# FET_bord.net
KiCad netlist of a schematic drawn in EAGLE
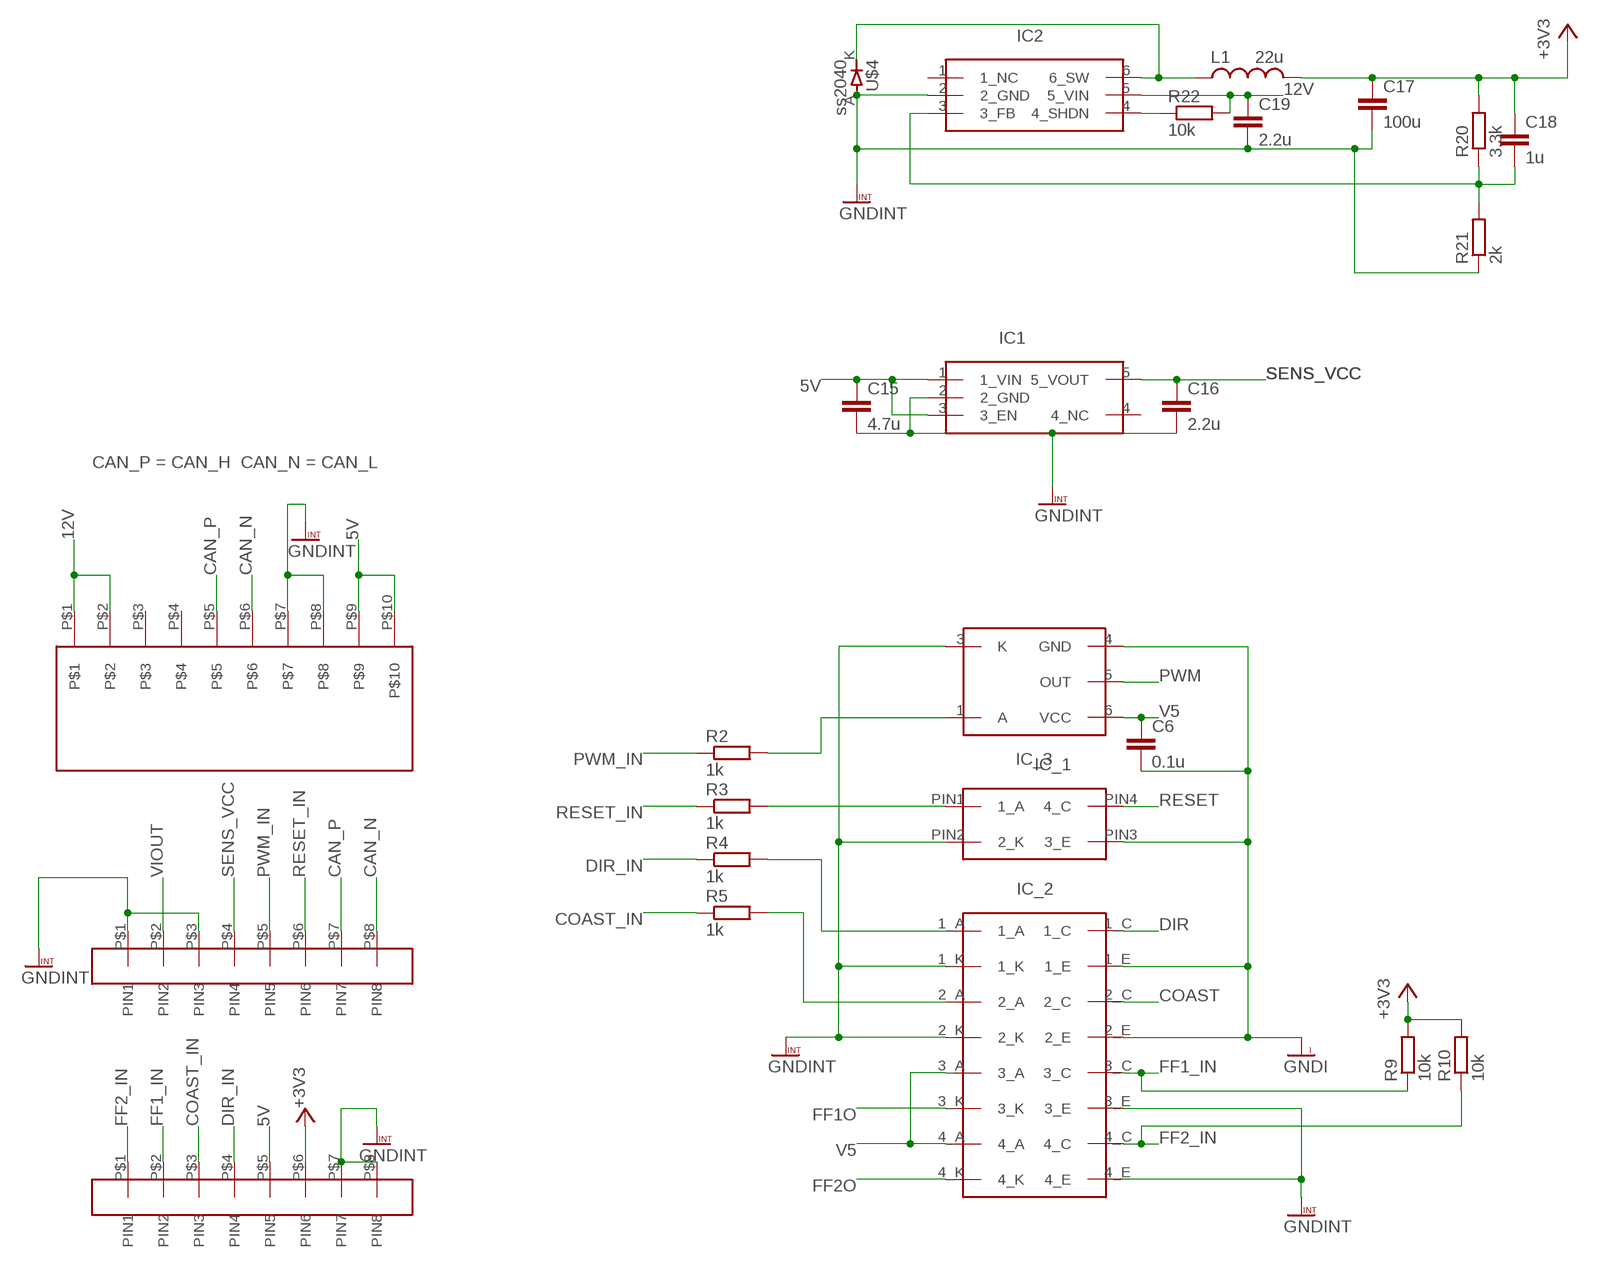
[diagram p0: schematic, sheet 1, part 1 of 2]
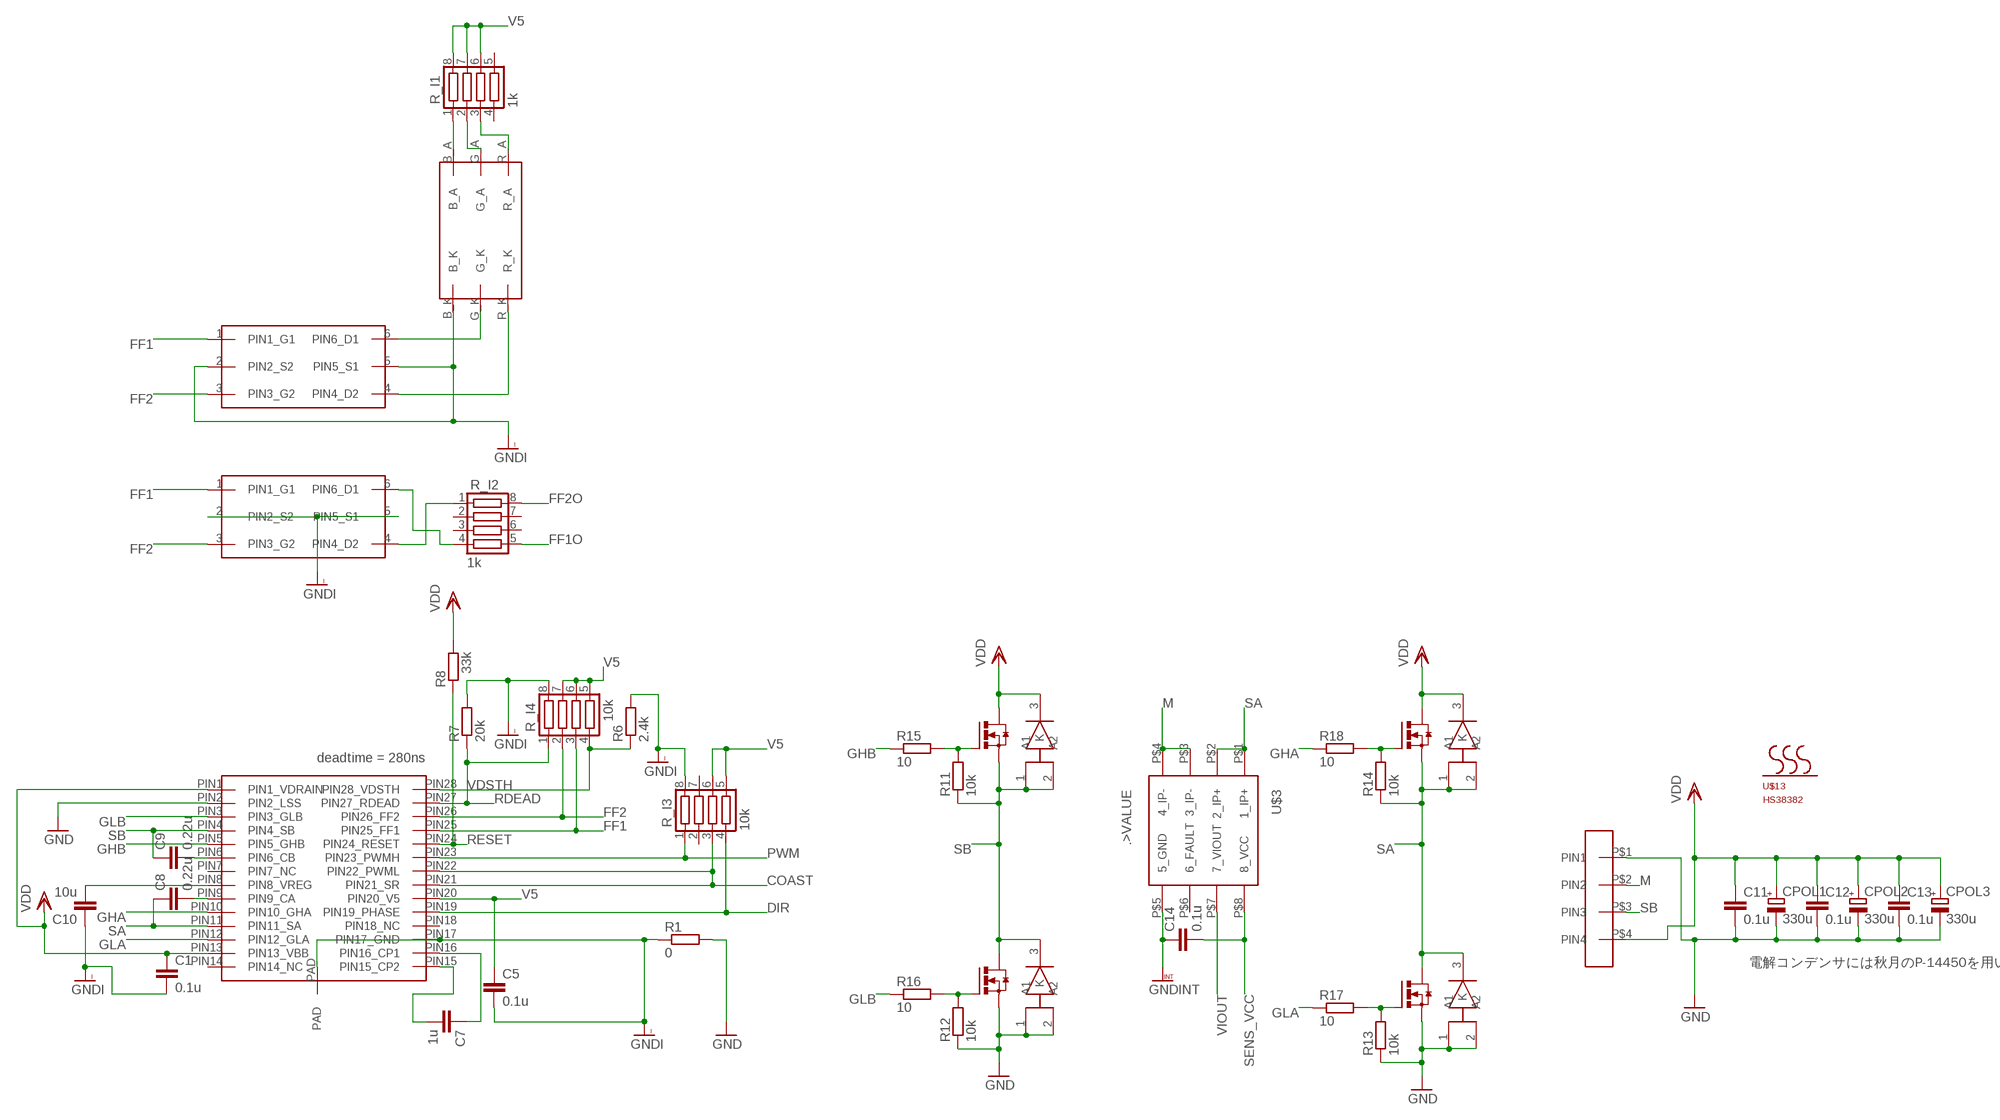
[diagram p1: schematic, sheet 1, part 2 of 2]

(export (version "E")
  (design (tool "Eeschema 10.0.6"))
  (components
    (comp (ref "C1")
      (value "0.1u")
      (footprint "eagle-import:C1608")
      (libsource (lib "eagle-import") (part "C-EUC1608"))
    )
    (comp (ref "C5")
      (value "0.1u")
      (footprint "eagle-import:C1608")
      (libsource (lib "eagle-import") (part "C-EUC1608"))
    )
    (comp (ref "C6")
      (value "0.1u")
      (footprint "eagle-import:C1608")
      (libsource (lib "eagle-import") (part "C-EUC1608"))
    )
    (comp (ref "C7")
      (value "1u")
      (footprint "eagle-import:C1608")
      (libsource (lib "eagle-import") (part "C-EUC1608"))
    )
    (comp (ref "C8")
      (value "0.22u")
      (footprint "eagle-import:C1608")
      (libsource (lib "eagle-import") (part "C-EUC1608"))
    )
    (comp (ref "C9")
      (value "0.22u")
      (footprint "eagle-import:C1608")
      (libsource (lib "eagle-import") (part "C-EUC1608"))
    )
    (comp (ref "C10")
      (value "10u")
      (footprint "eagle-import:C1608")
      (libsource (lib "eagle-import") (part "C-EUC1608"))
    )
    (comp (ref "C11")
      (value "0.1u")
      (footprint "eagle-import:C1608")
      (libsource (lib "eagle-import") (part "C-EUC1608"))
    )
    (comp (ref "C12")
      (value "0.1u")
      (footprint "eagle-import:C1608")
      (libsource (lib "eagle-import") (part "C-EUC1608"))
    )
    (comp (ref "C13")
      (value "0.1u")
      (footprint "eagle-import:C1608")
      (libsource (lib "eagle-import") (part "C-EUC1608"))
    )
    (comp (ref "C14")
      (value "0.1u")
      (footprint "eagle-import:C1608")
      (libsource (lib "eagle-import") (part "C-EUC1608"))
    )
    (comp (ref "C15")
      (value "4.7u")
      (footprint "eagle-import:C1608")
      (libsource (lib "eagle-import") (part "C-EUC1608"))
    )
    (comp (ref "C16")
      (value "2.2u")
      (footprint "eagle-import:C1608")
      (libsource (lib "eagle-import") (part "C-EUC1608"))
    )
    (comp (ref "C17")
      (value "100u")
      (footprint "eagle-import:C3216")
      (libsource (lib "eagle-import") (part "C-EUC3216"))
    )
    (comp (ref "C18")
      (value "1u")
      (footprint "eagle-import:C1608")
      (libsource (lib "eagle-import") (part "C-EUC1608"))
    )
    (comp (ref "C19")
      (value "2.2u")
      (footprint "eagle-import:C1608")
      (libsource (lib "eagle-import") (part "C-EUC1608"))
    )
    (comp (ref "CON1")
      (value "JQ_P8P")
      (footprint "eagle-import:JQ_P8P")
      (libsource (lib "eagle-import") (part "JQ_P8P"))
    )
    (comp (ref "CON2")
      (value "JQ_P8P")
      (footprint "eagle-import:JQ_P8P")
      (libsource (lib "eagle-import") (part "JQ_P8P"))
    )
    (comp (ref "CPOL1")
      (value "330u")
      (footprint "eagle-import:1014CAPA")
      (libsource (lib "eagle-import") (part "C_DEKAI"))
    )
    (comp (ref "CPOL2")
      (value "330u")
      (footprint "eagle-import:1014CAPA")
      (libsource (lib "eagle-import") (part "C_DEKAI"))
    )
    (comp (ref "CPOL3")
      (value "330u")
      (footprint "eagle-import:1014CAPA")
      (libsource (lib "eagle-import") (part "C_DEKAI"))
    )
    (comp (ref "IC1")
      (value "ADP151AUJZ")
      (footprint "eagle-import:SOT23-5")
      (libsource (lib "eagle-import") (part "ADP151AUJZ"))
    )
    (comp (ref "IC2")
      (value "NJW1616T")
      (footprint "eagle-import:SOT23-6")
      (libsource (lib "eagle-import") (part "NJW1616T"))
    )
    (comp (ref "IC_1")
      (value "TLP291")
      (footprint "eagle-import:TLP291")
      (libsource (lib "eagle-import") (part "TLP291"))
    )
    (comp (ref "IC_2")
      (value "TLP290-4")
      (footprint "eagle-import:TLP290")
      (libsource (lib "eagle-import") (part "TLP290-4"))
    )
    (comp (ref "IC_3")
      (value "TLP152")
      (footprint "eagle-import:SO6-5")
      (libsource (lib "eagle-import") (part "TLP152"))
    )
    (comp (ref "L1")
      (value "22u")
      (footprint "eagle-import:SMD_INDUCTOR")
      (libsource (lib "eagle-import") (part "L_SMD_INDUCTOR"))
    )
    (comp (ref "R1")
      (value "0")
      (footprint "eagle-import:1608")
      (libsource (lib "eagle-import") (part "R_REG"))
    )
    (comp (ref "R2")
      (value "1k")
      (footprint "eagle-import:1608")
      (libsource (lib "eagle-import") (part "R_REG"))
    )
    (comp (ref "R3")
      (value "1k")
      (footprint "eagle-import:1608")
      (libsource (lib "eagle-import") (part "R_REG"))
    )
    (comp (ref "R4")
      (value "1k")
      (footprint "eagle-import:1608")
      (libsource (lib "eagle-import") (part "R_REG"))
    )
    (comp (ref "R5")
      (value "1k")
      (footprint "eagle-import:1608")
      (libsource (lib "eagle-import") (part "R_REG"))
    )
    (comp (ref "R6")
      (value "2.4k")
      (footprint "eagle-import:1608")
      (libsource (lib "eagle-import") (part "R_REG"))
    )
    (comp (ref "R7")
      (value "20k")
      (footprint "eagle-import:1608")
      (libsource (lib "eagle-import") (part "R_REG"))
    )
    (comp (ref "R8")
      (value "33k")
      (footprint "eagle-import:1608")
      (libsource (lib "eagle-import") (part "R_REG"))
    )
    (comp (ref "R9")
      (value "10k")
      (footprint "eagle-import:1608")
      (libsource (lib "eagle-import") (part "R_REG"))
    )
    (comp (ref "R10")
      (value "10k")
      (footprint "eagle-import:1608")
      (libsource (lib "eagle-import") (part "R_REG"))
    )
    (comp (ref "R11")
      (value "10k")
      (footprint "eagle-import:1608")
      (libsource (lib "eagle-import") (part "R_REG"))
    )
    (comp (ref "R12")
      (value "10k")
      (footprint "eagle-import:1608")
      (libsource (lib "eagle-import") (part "R_REG"))
    )
    (comp (ref "R13")
      (value "10k")
      (footprint "eagle-import:1608")
      (libsource (lib "eagle-import") (part "R_REG"))
    )
    (comp (ref "R14")
      (value "10k")
      (footprint "eagle-import:1608")
      (libsource (lib "eagle-import") (part "R_REG"))
    )
    (comp (ref "R15")
      (value "10")
      (footprint "eagle-import:1608")
      (libsource (lib "eagle-import") (part "R_REG"))
    )
    (comp (ref "R16")
      (value "10")
      (footprint "eagle-import:1608")
      (libsource (lib "eagle-import") (part "R_REG"))
    )
    (comp (ref "R17")
      (value "10")
      (footprint "eagle-import:1608")
      (libsource (lib "eagle-import") (part "R_REG"))
    )
    (comp (ref "R18")
      (value "10")
      (footprint "eagle-import:1608")
      (libsource (lib "eagle-import") (part "R_REG"))
    )
    (comp (ref "R20")
      (value "3.3k")
      (footprint "eagle-import:1608")
      (libsource (lib "eagle-import") (part "R_REG"))
    )
    (comp (ref "R21")
      (value "2k")
      (footprint "eagle-import:1608")
      (libsource (lib "eagle-import") (part "R_REG"))
    )
    (comp (ref "R22")
      (value "10k")
      (footprint "eagle-import:1608")
      (libsource (lib "eagle-import") (part "R_REG"))
    )
    (comp (ref "R_I1")
      (value "1k")
      (footprint "eagle-import:0603X4RESISTOR")
      (libsource (lib "eagle-import") (part "R_SHUGOU"))
    )
    (comp (ref "R_I2")
      (value "1k")
      (footprint "eagle-import:0603X4RESISTOR")
      (libsource (lib "eagle-import") (part "R_SHUGOU"))
    )
    (comp (ref "R_I3")
      (value "10k")
      (footprint "eagle-import:1005X4RESISTOR")
      (libsource (lib "eagle-import") (part "R_SHUGOU2"))
    )
    (comp (ref "R_I4")
      (value "10k")
      (footprint "eagle-import:1005X4RESISTOR")
      (libsource (lib "eagle-import") (part "R_SHUGOU2"))
    )
    (comp (ref "TR1")
      (value "SKI03021")
      (footprint "eagle-import:D2PACK")
      (libsource (lib "eagle-import") (part "SKI03021"))
    )
    (comp (ref "TR2")
      (value "SKI03021")
      (footprint "eagle-import:D2PACK")
      (libsource (lib "eagle-import") (part "SKI03021"))
    )
    (comp (ref "TR3")
      (value "SKI03021")
      (footprint "eagle-import:D2PACK")
      (libsource (lib "eagle-import") (part "SKI03021"))
    )
    (comp (ref "TR4")
      (value "SKI03021")
      (footprint "eagle-import:D2PACK")
      (libsource (lib "eagle-import") (part "SKI03021"))
    )
    (comp (ref "U$1")
      (value "VL_4P")
      (footprint "eagle-import:VL_4P")
      (libsource (lib "eagle-import") (part "VL_4P"))
    )
    (comp (ref "U$2")
      (value "A3921")
      (footprint "eagle-import:TSSOP_28P_ALLEGRO")
      (libsource (lib "eagle-import") (part "A3921"))
    )
    (comp (ref "U$3")
      (value "ACS711")
      (footprint "eagle-import:SOIC8")
      (libsource (lib "eagle-import") (part "ACS711"))
    )
    (comp (ref "U$4")
      (value "ss2040")
      (footprint "eagle-import:SOD_123")
      (libsource (lib "eagle-import") (part "SMD_DAIOD"))
    )
    (comp (ref "U$5")
      (value "FDC6305")
      (footprint "eagle-import:SSOT6")
      (libsource (lib "eagle-import") (part "FDC6305"))
    )
    (comp (ref "U$6")
      (value "RGB_LED")
      (footprint "eagle-import:RGB_LED")
      (libsource (lib "eagle-import") (part "RGB_LED"))
    )
    (comp (ref "U$7")
      (value "FDC6305")
      (footprint "eagle-import:SSOT6")
      (libsource (lib "eagle-import") (part "FDC6305"))
    )
    (comp (ref "U$8")
      (value "BOX10PBOX10P-L")
      (footprint "eagle-import:BOX10P-L")
      (libsource (lib "eagle-import") (part "BOX10PBOX10P-L"))
    )
    (comp (ref "U$9")
      (value "SBR15U30SP5")
      (footprint "eagle-import:POWERDI_5")
      (libsource (lib "eagle-import") (part "SBR15U30SP5"))
    )
    (comp (ref "U$10")
      (value "SBR15U30SP5")
      (footprint "eagle-import:POWERDI_5")
      (libsource (lib "eagle-import") (part "SBR15U30SP5"))
    )
    (comp (ref "U$11")
      (value "SBR15U30SP5")
      (footprint "eagle-import:POWERDI_5")
      (libsource (lib "eagle-import") (part "SBR15U30SP5"))
    )
    (comp (ref "U$12")
      (value "SBR15U30SP5")
      (footprint "eagle-import:POWERDI_5")
      (libsource (lib "eagle-import") (part "SBR15U30SP5"))
    )
    (comp (ref "U$13")
      (value "HS38382")
      (footprint "eagle-import:38X38SQ")
      (libsource (lib "eagle-import") (part "HS38382"))
    )
  )
  (nets
    (net (code "1") (name "+3V3") (class "Default")
      (node (ref "C17") (pin "1") (pinfunction "1_1") (pintype "passive"))
      (node (ref "C18") (pin "1") (pinfunction "1_1") (pintype "passive"))
      (node (ref "CON1") (pin "P$6") (pinfunction "PIN6_P$6") (pintype "bidirectional"))
      (node (ref "L1") (pin "P$2") (pinfunction "2_P$2") (pintype "passive"))
      (node (ref "R10") (pin "2") (pinfunction "2_2") (pintype "passive"))
      (node (ref "R20") (pin "2") (pinfunction "2_2") (pintype "passive"))
      (node (ref "R9") (pin "2") (pinfunction "2_2") (pintype "passive"))
    )
    (net (code "2") (name "/5V") (class "Default")
      (node (ref "C15") (pin "1") (pinfunction "1_1") (pintype "passive"))
      (node (ref "CON1") (pin "P$5") (pinfunction "PIN5_P$5") (pintype "bidirectional"))
      (node (ref "IC1") (pin "1") (pinfunction "1_VIN_1") (pintype "bidirectional"))
      (node (ref "IC1") (pin "3") (pinfunction "3_EN_3") (pintype "bidirectional"))
      (node (ref "U$8") (pin "P$10") (pinfunction "P$10_P$10") (pintype "bidirectional"))
      (node (ref "U$8") (pin "P$9") (pinfunction "P$9_P$9") (pintype "bidirectional"))
    )
    (net (code "3") (name "/12V") (class "Default")
      (node (ref "C19") (pin "1") (pinfunction "1_1") (pintype "passive"))
      (node (ref "IC2") (pin "5") (pinfunction "5_VIN_5") (pintype "bidirectional"))
      (node (ref "R22") (pin "2") (pinfunction "2_2") (pintype "passive"))
      (node (ref "U$8") (pin "P$1") (pinfunction "P$1_P$1") (pintype "bidirectional"))
      (node (ref "U$8") (pin "P$2") (pinfunction "P$2_P$2") (pintype "bidirectional"))
    )
    (net (code "4") (name "/CAN_N") (class "Default")
      (node (ref "CON2") (pin "P$8") (pinfunction "PIN8_P$8") (pintype "bidirectional"))
      (node (ref "U$8") (pin "P$6") (pinfunction "P$6_P$6") (pintype "bidirectional"))
    )
    (net (code "5") (name "/CAN_P") (class "Default")
      (node (ref "CON2") (pin "P$7") (pinfunction "PIN7_P$7") (pintype "bidirectional"))
      (node (ref "U$8") (pin "P$5") (pinfunction "P$5_P$5") (pintype "bidirectional"))
    )
    (net (code "6") (name "/COAST") (class "Default")
      (node (ref "IC_2") (pin "2_C") (pinfunction "2_C_2_C") (pintype "bidirectional"))
      (node (ref "R_I3") (pin "3") (pinfunction "3_3") (pintype "passive"))
      (node (ref "U$2") (pin "PIN21") (pinfunction "PIN21_SR_PIN21") (pintype "bidirectional"))
      (node (ref "U$2") (pin "PIN22") (pinfunction "PIN22_PWML_PIN22") (pintype "bidirectional"))
    )
    (net (code "7") (name "/COAST_IN") (class "Default")
      (node (ref "CON1") (pin "P$3") (pinfunction "PIN3_P$3") (pintype "bidirectional"))
      (node (ref "R5") (pin "1") (pinfunction "1_1") (pintype "passive"))
    )
    (net (code "8") (name "/DIR") (class "Default")
      (node (ref "IC_2") (pin "1_C") (pinfunction "1_C_1_C") (pintype "bidirectional"))
      (node (ref "R_I3") (pin "4") (pinfunction "4_4") (pintype "passive"))
      (node (ref "U$2") (pin "PIN19") (pinfunction "PIN19_PHASE_PIN19") (pintype "bidirectional"))
    )
    (net (code "9") (name "/DIR_IN") (class "Default")
      (node (ref "CON1") (pin "P$4") (pinfunction "PIN4_P$4") (pintype "bidirectional"))
      (node (ref "R4") (pin "1") (pinfunction "1_1") (pintype "passive"))
    )
    (net (code "10") (name "/FF1") (class "Default")
      (node (ref "R_I4") (pin "3") (pinfunction "3_3") (pintype "passive"))
      (node (ref "U$2") (pin "PIN25") (pinfunction "PIN25_FF1_PIN25") (pintype "bidirectional"))
      (node (ref "U$5") (pin "1") (pinfunction "PIN1_G1_1") (pintype "bidirectional"))
      (node (ref "U$7") (pin "1") (pinfunction "PIN1_G1_1") (pintype "bidirectional"))
    )
    (net (code "11") (name "/FF1O") (class "Default")
      (node (ref "IC_2") (pin "3_K") (pinfunction "3_K_3_K") (pintype "bidirectional"))
      (node (ref "R_I2") (pin "5") (pinfunction "5_5") (pintype "passive"))
    )
    (net (code "12") (name "/FF1_IN") (class "Default")
      (node (ref "CON1") (pin "P$2") (pinfunction "PIN2_P$2") (pintype "bidirectional"))
      (node (ref "IC_2") (pin "3_C") (pinfunction "3_C_3_C") (pintype "bidirectional"))
      (node (ref "R9") (pin "1") (pinfunction "1_1") (pintype "passive"))
    )
    (net (code "13") (name "/FF2") (class "Default")
      (node (ref "R_I4") (pin "2") (pinfunction "2_2") (pintype "passive"))
      (node (ref "U$2") (pin "PIN26") (pinfunction "PIN26_FF2_PIN26") (pintype "bidirectional"))
      (node (ref "U$5") (pin "3") (pinfunction "PIN3_G2_3") (pintype "bidirectional"))
      (node (ref "U$7") (pin "3") (pinfunction "PIN3_G2_3") (pintype "bidirectional"))
    )
    (net (code "14") (name "/FF2O") (class "Default")
      (node (ref "IC_2") (pin "4_K") (pinfunction "4_K_4_K") (pintype "bidirectional"))
      (node (ref "R_I2") (pin "8") (pinfunction "8_8") (pintype "passive"))
    )
    (net (code "15") (name "/FF2_IN") (class "Default")
      (node (ref "CON1") (pin "P$1") (pinfunction "PIN1_P$1") (pintype "bidirectional"))
      (node (ref "IC_2") (pin "4_C") (pinfunction "4_C_4_C") (pintype "bidirectional"))
      (node (ref "R10") (pin "1") (pinfunction "1_1") (pintype "passive"))
    )
    (net (code "16") (name "/GHA") (class "Default")
      (node (ref "R18") (pin "1") (pinfunction "1_1") (pintype "passive"))
      (node (ref "U$2") (pin "PIN10") (pinfunction "PIN10_GHA_PIN10") (pintype "bidirectional"))
    )
    (net (code "17") (name "/GHB") (class "Default")
      (node (ref "R15") (pin "1") (pinfunction "1_1") (pintype "passive"))
      (node (ref "U$2") (pin "PIN5") (pinfunction "PIN5_GHB_PIN5") (pintype "bidirectional"))
    )
    (net (code "18") (name "/GLA") (class "Default")
      (node (ref "R17") (pin "1") (pinfunction "1_1") (pintype "passive"))
      (node (ref "U$2") (pin "PIN12") (pinfunction "PIN12_GLA_PIN12") (pintype "bidirectional"))
    )
    (net (code "19") (name "/GLB") (class "Default")
      (node (ref "R16") (pin "1") (pinfunction "1_1") (pintype "passive"))
      (node (ref "U$2") (pin "PIN3") (pinfunction "PIN3_GLB_PIN3") (pintype "bidirectional"))
    )
    (net (code "20") (name "/M") (class "Default")
      (node (ref "U$1") (pin "P$2") (pinfunction "PIN2_P$2") (pintype "bidirectional"))
      (node (ref "U$3") (pin "P$3") (pinfunction "3_IP-_P$3") (pintype "bidirectional"))
      (node (ref "U$3") (pin "P$4") (pinfunction "4_IP-_P$4") (pintype "bidirectional"))
    )
    (net (code "21") (name "/PWM") (class "Default")
      (node (ref "IC_3") (pin "5") (pinfunction "OUT_5") (pintype "bidirectional"))
      (node (ref "R_I3") (pin "1") (pinfunction "1_1") (pintype "passive"))
      (node (ref "U$2") (pin "PIN23") (pinfunction "PIN23_PWMH_PIN23") (pintype "bidirectional"))
    )
    (net (code "22") (name "/PWM_IN") (class "Default")
      (node (ref "CON2") (pin "P$5") (pinfunction "PIN5_P$5") (pintype "bidirectional"))
      (node (ref "R2") (pin "1") (pinfunction "1_1") (pintype "passive"))
    )
    (net (code "23") (name "/RDEAD") (class "Default")
      (node (ref "R7") (pin "1") (pinfunction "1_1") (pintype "passive"))
      (node (ref "R_I4") (pin "1") (pinfunction "1_1") (pintype "passive"))
      (node (ref "U$2") (pin "PIN27") (pinfunction "PIN27_RDEAD_PIN27") (pintype "bidirectional"))
    )
    (net (code "24") (name "/RESET") (class "Default")
      (node (ref "IC_1") (pin "PIN4") (pinfunction "4_C_PIN4") (pintype "bidirectional"))
      (node (ref "R8") (pin "1") (pinfunction "1_1") (pintype "passive"))
      (node (ref "U$2") (pin "PIN24") (pinfunction "PIN24_RESET_PIN24") (pintype "bidirectional"))
    )
    (net (code "25") (name "/RESET_IN") (class "Default")
      (node (ref "CON2") (pin "P$6") (pinfunction "PIN6_P$6") (pintype "bidirectional"))
      (node (ref "R3") (pin "1") (pinfunction "1_1") (pintype "passive"))
    )
    (net (code "26") (name "/SA") (class "Default")
      (node (ref "C8") (pin "1") (pinfunction "1_1") (pintype "passive"))
      (node (ref "R14") (pin "1") (pinfunction "1_1") (pintype "passive"))
      (node (ref "TR2") (pin "3") (pinfunction "PIN3_S_3") (pintype "passive"))
      (node (ref "TR4") (pin "2") (pinfunction "PIN2_D_2") (pintype "passive"))
      (node (ref "U$11") (pin "3") (pinfunction "K_3") (pintype "bidirectional"))
      (node (ref "U$12") (pin "1") (pinfunction "A1_1") (pintype "bidirectional"))
      (node (ref "U$12") (pin "2") (pinfunction "A2_2") (pintype "bidirectional"))
      (node (ref "U$2") (pin "PIN11") (pinfunction "PIN11_SA_PIN11") (pintype "bidirectional"))
      (node (ref "U$3") (pin "P$1") (pinfunction "1_IP+_P$1") (pintype "bidirectional"))
      (node (ref "U$3") (pin "P$2") (pinfunction "2_IP+_P$2") (pintype "bidirectional"))
    )
    (net (code "27") (name "/SB") (class "Default")
      (node (ref "C9") (pin "1") (pinfunction "1_1") (pintype "passive"))
      (node (ref "R11") (pin "1") (pinfunction "1_1") (pintype "passive"))
      (node (ref "TR1") (pin "3") (pinfunction "PIN3_S_3") (pintype "passive"))
      (node (ref "TR3") (pin "2") (pinfunction "PIN2_D_2") (pintype "passive"))
      (node (ref "U$1") (pin "P$3") (pinfunction "PIN3_P$3") (pintype "bidirectional"))
      (node (ref "U$10") (pin "3") (pinfunction "K_3") (pintype "bidirectional"))
      (node (ref "U$2") (pin "PIN4") (pinfunction "PIN4_SB_PIN4") (pintype "bidirectional"))
      (node (ref "U$9") (pin "1") (pinfunction "A1_1") (pintype "bidirectional"))
      (node (ref "U$9") (pin "2") (pinfunction "A2_2") (pintype "bidirectional"))
    )
    (net (code "28") (name "/SENS_VCC") (class "Default")
      (node (ref "C14") (pin "2") (pinfunction "2_2") (pintype "passive"))
      (node (ref "C16") (pin "1") (pinfunction "1_1") (pintype "passive"))
      (node (ref "CON2") (pin "P$4") (pinfunction "PIN4_P$4") (pintype "bidirectional"))
      (node (ref "IC1") (pin "5") (pinfunction "5_VOUT_5") (pintype "bidirectional"))
      (node (ref "U$3") (pin "P$8") (pinfunction "8_VCC_P$8") (pintype "bidirectional"))
    )
    (net (code "29") (name "/V5") (class "Default")
      (node (ref "C5") (pin "1") (pinfunction "1_1") (pintype "passive"))
      (node (ref "C6") (pin "1") (pinfunction "1_1") (pintype "passive"))
      (node (ref "IC_2") (pin "3_A") (pinfunction "3_A_3_A") (pintype "bidirectional"))
      (node (ref "IC_2") (pin "4_A") (pinfunction "4_A_4_A") (pintype "bidirectional"))
      (node (ref "IC_3") (pin "6") (pinfunction "VCC_6") (pintype "bidirectional"))
      (node (ref "R_I1") (pin "6") (pinfunction "6_6") (pintype "passive"))
      (node (ref "R_I1") (pin "7") (pinfunction "7_7") (pintype "passive"))
      (node (ref "R_I1") (pin "8") (pinfunction "8_8") (pintype "passive"))
      (node (ref "R_I3") (pin "5") (pinfunction "5_5") (pintype "passive"))
      (node (ref "R_I3") (pin "6") (pinfunction "6_6") (pintype "passive"))
      (node (ref "R_I4") (pin "5") (pinfunction "5_5") (pintype "passive"))
      (node (ref "R_I4") (pin "6") (pinfunction "6_6") (pintype "passive"))
      (node (ref "R_I4") (pin "7") (pinfunction "7_7") (pintype "passive"))
      (node (ref "U$2") (pin "PIN20") (pinfunction "PIN20_V5_PIN20") (pintype "bidirectional"))
    )
    (net (code "30") (name "/VDSTH") (class "Default")
      (node (ref "R6") (pin "1") (pinfunction "1_1") (pintype "passive"))
      (node (ref "R_I4") (pin "4") (pinfunction "4_4") (pintype "passive"))
      (node (ref "U$2") (pin "PIN28") (pinfunction "PIN28_VDSTH_PIN28") (pintype "bidirectional"))
    )
    (net (code "31") (name "/VIOUT") (class "Default")
      (node (ref "CON2") (pin "P$2") (pinfunction "PIN2_P$2") (pintype "bidirectional"))
      (node (ref "U$3") (pin "P$7") (pinfunction "7_VIOUT_P$7") (pintype "bidirectional"))
    )
    (net (code "32") (name "GND") (class "Default")
      (node (ref "C11") (pin "2") (pinfunction "2_2") (pintype "passive"))
      (node (ref "C12") (pin "2") (pinfunction "2_2") (pintype "passive"))
      (node (ref "C13") (pin "2") (pinfunction "2_2") (pintype "passive"))
      (node (ref "CPOL1") (pin "-") (pinfunction "-_-") (pintype "passive"))
      (node (ref "CPOL2") (pin "-") (pinfunction "-_-") (pintype "passive"))
      (node (ref "CPOL3") (pin "-") (pinfunction "-_-") (pintype "passive"))
      (node (ref "R1") (pin "2") (pinfunction "2_2") (pintype "passive"))
      (node (ref "R12") (pin "1") (pinfunction "1_1") (pintype "passive"))
      (node (ref "R13") (pin "1") (pinfunction "1_1") (pintype "passive"))
      (node (ref "TR3") (pin "3") (pinfunction "PIN3_S_3") (pintype "passive"))
      (node (ref "TR4") (pin "3") (pinfunction "PIN3_S_3") (pintype "passive"))
      (node (ref "U$1") (pin "P$1") (pinfunction "PIN1_P$1") (pintype "bidirectional"))
      (node (ref "U$10") (pin "1") (pinfunction "A1_1") (pintype "bidirectional"))
      (node (ref "U$10") (pin "2") (pinfunction "A2_2") (pintype "bidirectional"))
      (node (ref "U$11") (pin "1") (pinfunction "A1_1") (pintype "bidirectional"))
      (node (ref "U$11") (pin "2") (pinfunction "A2_2") (pintype "bidirectional"))
      (node (ref "U$2") (pin "PIN2") (pinfunction "PIN2_LSS_PIN2") (pintype "bidirectional"))
    )
    (net (code "33") (name "GNDI") (class "Default")
      (node (ref "C1") (pin "2") (pinfunction "2_2") (pintype "passive"))
      (node (ref "C10") (pin "1") (pinfunction "1_1") (pintype "passive"))
      (node (ref "C5") (pin "2") (pinfunction "2_2") (pintype "passive"))
      (node (ref "C6") (pin "2") (pinfunction "2_2") (pintype "passive"))
      (node (ref "IC_1") (pin "PIN3") (pinfunction "3_E_PIN3") (pintype "bidirectional"))
      (node (ref "IC_2") (pin "1_E") (pinfunction "1_E_1_E") (pintype "bidirectional"))
      (node (ref "IC_2") (pin "2_E") (pinfunction "2_E_2_E") (pintype "bidirectional"))
      (node (ref "IC_3") (pin "4") (pinfunction "GND_4") (pintype "bidirectional"))
      (node (ref "R1") (pin "1") (pinfunction "1_1") (pintype "passive"))
      (node (ref "R6") (pin "2") (pinfunction "2_2") (pintype "passive"))
      (node (ref "R7") (pin "2") (pinfunction "2_2") (pintype "passive"))
      (node (ref "R_I3") (pin "8") (pinfunction "8_8") (pintype "passive"))
      (node (ref "R_I4") (pin "8") (pinfunction "8_8") (pintype "passive"))
      (node (ref "U$2") (pin "PAD") (pinfunction "PAD_PAD") (pintype "bidirectional"))
      (node (ref "U$2") (pin "PIN17") (pinfunction "PIN17_GND_PIN17") (pintype "bidirectional"))
      (node (ref "U$5") (pin "2") (pinfunction "PIN2_S2_2") (pintype "bidirectional"))
      (node (ref "U$5") (pin "5") (pinfunction "PIN5_S1_5") (pintype "bidirectional"))
      (node (ref "U$6") (pin "B_K") (pinfunction "B_K_B_K") (pintype "bidirectional"))
      (node (ref "U$7") (pin "2") (pinfunction "PIN2_S2_2") (pintype "bidirectional"))
      (node (ref "U$7") (pin "5") (pinfunction "PIN5_S1_5") (pintype "bidirectional"))
    )
    (net (code "34") (name "GNDINT") (class "Default")
      (node (ref "C14") (pin "1") (pinfunction "1_1") (pintype "passive"))
      (node (ref "C15") (pin "2") (pinfunction "2_2") (pintype "passive"))
      (node (ref "C16") (pin "2") (pinfunction "2_2") (pintype "passive"))
      (node (ref "C17") (pin "2") (pinfunction "2_2") (pintype "passive"))
      (node (ref "C19") (pin "2") (pinfunction "2_2") (pintype "passive"))
      (node (ref "CON1") (pin "P$7") (pinfunction "PIN7_P$7") (pintype "bidirectional"))
      (node (ref "CON1") (pin "P$8") (pinfunction "PIN8_P$8") (pintype "bidirectional"))
      (node (ref "CON2") (pin "P$1") (pinfunction "PIN1_P$1") (pintype "bidirectional"))
      (node (ref "CON2") (pin "P$3") (pinfunction "PIN3_P$3") (pintype "bidirectional"))
      (node (ref "IC1") (pin "2") (pinfunction "2_GND_2") (pintype "bidirectional"))
      (node (ref "IC2") (pin "2") (pinfunction "2_GND_2") (pintype "bidirectional"))
      (node (ref "IC_1") (pin "PIN2") (pinfunction "2_K_PIN2") (pintype "bidirectional"))
      (node (ref "IC_2") (pin "1_K") (pinfunction "1_K_1_K") (pintype "bidirectional"))
      (node (ref "IC_2") (pin "2_K") (pinfunction "2_K_2_K") (pintype "bidirectional"))
      (node (ref "IC_2") (pin "3_E") (pinfunction "3_E_3_E") (pintype "bidirectional"))
      (node (ref "IC_2") (pin "4_E") (pinfunction "4_E_4_E") (pintype "bidirectional"))
      (node (ref "IC_3") (pin "3") (pinfunction "K_3") (pintype "bidirectional"))
      (node (ref "R21") (pin "1") (pinfunction "1_1") (pintype "passive"))
      (node (ref "U$3") (pin "P$5") (pinfunction "5_GND_P$5") (pintype "bidirectional"))
      (node (ref "U$4") (pin "A") (pinfunction "A_A") (pintype "passive"))
      (node (ref "U$8") (pin "P$7") (pinfunction "P$7_P$7") (pintype "bidirectional"))
      (node (ref "U$8") (pin "P$8") (pinfunction "P$8_P$8") (pintype "bidirectional"))
    )
    (net (code "35") (name "Net-(IC2-3_FB)") (class "Default")
      (node (ref "C18") (pin "2") (pinfunction "2_2") (pintype "passive"))
      (node (ref "IC2") (pin "3") (pinfunction "3_FB_3") (pintype "bidirectional"))
      (node (ref "R20") (pin "1") (pinfunction "1_1") (pintype "passive"))
      (node (ref "R21") (pin "2") (pinfunction "2_2") (pintype "passive"))
    )
    (net (code "36") (name "Net-(IC2-4_SHDN)") (class "Default")
      (node (ref "IC2") (pin "4") (pinfunction "4_SHDN_4") (pintype "bidirectional"))
      (node (ref "R22") (pin "1") (pinfunction "1_1") (pintype "passive"))
    )
    (net (code "37") (name "Net-(IC2-6_SW)") (class "Default")
      (node (ref "IC2") (pin "6") (pinfunction "6_SW_6") (pintype "bidirectional"))
      (node (ref "L1") (pin "P$1") (pinfunction "1_P$1") (pintype "passive"))
      (node (ref "U$4") (pin "K") (pinfunction "C_K") (pintype "passive"))
    )
    (net (code "38") (name "Net-(IC_1-1_A)") (class "Default")
      (node (ref "IC_1") (pin "PIN1") (pinfunction "1_A_PIN1") (pintype "bidirectional"))
      (node (ref "R3") (pin "2") (pinfunction "2_2") (pintype "passive"))
    )
    (net (code "39") (name "Net-(IC_2-Pad1_A)") (class "Default")
      (node (ref "IC_2") (pin "1_A") (pinfunction "1_A_1_A") (pintype "bidirectional"))
      (node (ref "R4") (pin "2") (pinfunction "2_2") (pintype "passive"))
    )
    (net (code "40") (name "Net-(IC_2-Pad2_A)") (class "Default")
      (node (ref "IC_2") (pin "2_A") (pinfunction "2_A_2_A") (pintype "bidirectional"))
      (node (ref "R5") (pin "2") (pinfunction "2_2") (pintype "passive"))
    )
    (net (code "41") (name "Net-(IC_3-A)") (class "Default")
      (node (ref "IC_3") (pin "1") (pinfunction "A_1") (pintype "bidirectional"))
      (node (ref "R2") (pin "2") (pinfunction "2_2") (pintype "passive"))
    )
    (net (code "42") (name "Net-(R_I1-Pad1)") (class "Default")
      (node (ref "R_I1") (pin "1") (pinfunction "1_1") (pintype "passive"))
      (node (ref "U$6") (pin "B_A") (pinfunction "B_A_B_A") (pintype "bidirectional"))
    )
    (net (code "43") (name "Net-(R_I1-Pad2)") (class "Default")
      (node (ref "R_I1") (pin "2") (pinfunction "2_2") (pintype "passive"))
      (node (ref "U$6") (pin "G_A") (pinfunction "G_A_G_A") (pintype "bidirectional"))
    )
    (net (code "44") (name "Net-(R_I1-Pad3)") (class "Default")
      (node (ref "R_I1") (pin "3") (pinfunction "3_3") (pintype "passive"))
      (node (ref "U$6") (pin "R_A") (pinfunction "R_A_R_A") (pintype "bidirectional"))
    )
    (net (code "45") (name "Net-(TR1-PIN1_G)") (class "Default")
      (node (ref "R11") (pin "2") (pinfunction "2_2") (pintype "passive"))
      (node (ref "R15") (pin "2") (pinfunction "2_2") (pintype "passive"))
      (node (ref "TR1") (pin "1") (pinfunction "PIN1_G_1") (pintype "passive"))
    )
    (net (code "46") (name "Net-(TR2-PIN1_G)") (class "Default")
      (node (ref "R14") (pin "2") (pinfunction "2_2") (pintype "passive"))
      (node (ref "R18") (pin "2") (pinfunction "2_2") (pintype "passive"))
      (node (ref "TR2") (pin "1") (pinfunction "PIN1_G_1") (pintype "passive"))
    )
    (net (code "47") (name "Net-(TR3-PIN1_G)") (class "Default")
      (node (ref "R12") (pin "2") (pinfunction "2_2") (pintype "passive"))
      (node (ref "R16") (pin "2") (pinfunction "2_2") (pintype "passive"))
      (node (ref "TR3") (pin "1") (pinfunction "PIN1_G_1") (pintype "passive"))
    )
    (net (code "48") (name "Net-(TR4-PIN1_G)") (class "Default")
      (node (ref "R13") (pin "2") (pinfunction "2_2") (pintype "passive"))
      (node (ref "R17") (pin "2") (pinfunction "2_2") (pintype "passive"))
      (node (ref "TR4") (pin "1") (pinfunction "PIN1_G_1") (pintype "passive"))
    )
    (net (code "49") (name "Net-(U$2-PIN6_CB)") (class "Default")
      (node (ref "C9") (pin "2") (pinfunction "2_2") (pintype "passive"))
      (node (ref "U$2") (pin "PIN6") (pinfunction "PIN6_CB_PIN6") (pintype "bidirectional"))
    )
    (net (code "50") (name "Net-(U$2-PIN8_VREG)") (class "Default")
      (node (ref "C10") (pin "2") (pinfunction "2_2") (pintype "passive"))
      (node (ref "U$2") (pin "PIN8") (pinfunction "PIN8_VREG_PIN8") (pintype "bidirectional"))
    )
    (net (code "51") (name "Net-(U$2-PIN9_CA)") (class "Default")
      (node (ref "C8") (pin "2") (pinfunction "2_2") (pintype "passive"))
      (node (ref "U$2") (pin "PIN9") (pinfunction "PIN9_CA_PIN9") (pintype "bidirectional"))
    )
    (net (code "52") (name "Net-(U$2-PIN15_CP2)") (class "Default")
      (node (ref "C7") (pin "2") (pinfunction "2_2") (pintype "passive"))
      (node (ref "U$2") (pin "PIN15") (pinfunction "PIN15_CP2_PIN15") (pintype "bidirectional"))
    )
    (net (code "53") (name "Net-(U$2-PIN16_CP1)") (class "Default")
      (node (ref "C7") (pin "1") (pinfunction "1_1") (pintype "passive"))
      (node (ref "U$2") (pin "PIN16") (pinfunction "PIN16_CP1_PIN16") (pintype "bidirectional"))
    )
    (net (code "54") (name "Net-(U$5-PIN4_D2)") (class "Default")
      (node (ref "U$5") (pin "4") (pinfunction "PIN4_D2_4") (pintype "bidirectional"))
      (node (ref "U$6") (pin "R_K") (pinfunction "R_K_R_K") (pintype "bidirectional"))
    )
    (net (code "55") (name "Net-(U$5-PIN6_D1)") (class "Default")
      (node (ref "U$5") (pin "6") (pinfunction "PIN6_D1_6") (pintype "bidirectional"))
      (node (ref "U$6") (pin "G_K") (pinfunction "G_K_G_K") (pintype "bidirectional"))
    )
    (net (code "56") (name "Net-(U$7-PIN4_D2)") (class "Default")
      (node (ref "R_I2") (pin "1") (pinfunction "1_1") (pintype "passive"))
      (node (ref "U$7") (pin "4") (pinfunction "PIN4_D2_4") (pintype "bidirectional"))
    )
    (net (code "57") (name "Net-(U$7-PIN6_D1)") (class "Default")
      (node (ref "R_I2") (pin "4") (pinfunction "4_4") (pintype "passive"))
      (node (ref "U$7") (pin "6") (pinfunction "PIN6_D1_6") (pintype "bidirectional"))
    )
    (net (code "58") (name "VDD") (class "Default")
      (node (ref "C1") (pin "1") (pinfunction "1_1") (pintype "passive"))
      (node (ref "C11") (pin "1") (pinfunction "1_1") (pintype "passive"))
      (node (ref "C12") (pin "1") (pinfunction "1_1") (pintype "passive"))
      (node (ref "C13") (pin "1") (pinfunction "1_1") (pintype "passive"))
      (node (ref "CPOL1") (pin "+") (pinfunction "+_+") (pintype "passive"))
      (node (ref "CPOL2") (pin "+") (pinfunction "+_+") (pintype "passive"))
      (node (ref "CPOL3") (pin "+") (pinfunction "+_+") (pintype "passive"))
      (node (ref "R8") (pin "2") (pinfunction "2_2") (pintype "passive"))
      (node (ref "TR1") (pin "2") (pinfunction "PIN2_D_2") (pintype "passive"))
      (node (ref "TR2") (pin "2") (pinfunction "PIN2_D_2") (pintype "passive"))
      (node (ref "U$1") (pin "P$4") (pinfunction "PIN4_P$4") (pintype "bidirectional"))
      (node (ref "U$12") (pin "3") (pinfunction "K_3") (pintype "bidirectional"))
      (node (ref "U$2") (pin "PIN1") (pinfunction "PIN1_VDRAIN_PIN1") (pintype "bidirectional"))
      (node (ref "U$2") (pin "PIN13") (pinfunction "PIN13_VBB_PIN13") (pintype "bidirectional"))
      (node (ref "U$9") (pin "3") (pinfunction "K_3") (pintype "bidirectional"))
    )
    (net (code "59") (name "unconnected-(IC1-4_NC-Pad4)") (class "Default")
      (node (ref "IC1") (pin "4") (pinfunction "4_NC_4") (pintype "bidirectional"))
    )
    (net (code "60") (name "unconnected-(IC2-1_NC-Pad1)") (class "Default")
      (node (ref "IC2") (pin "1") (pinfunction "1_NC_1") (pintype "bidirectional"))
    )
    (net (code "61") (name "unconnected-(R_I1-Pad4)") (class "Default")
      (node (ref "R_I1") (pin "4") (pinfunction "4_4") (pintype "passive"))
    )
    (net (code "62") (name "unconnected-(R_I1-Pad5)") (class "Default")
      (node (ref "R_I1") (pin "5") (pinfunction "5_5") (pintype "passive"))
    )
    (net (code "63") (name "unconnected-(R_I2-Pad2)") (class "Default")
      (node (ref "R_I2") (pin "2") (pinfunction "2_2") (pintype "passive"))
    )
    (net (code "64") (name "unconnected-(R_I2-Pad3)") (class "Default")
      (node (ref "R_I2") (pin "3") (pinfunction "3_3") (pintype "passive"))
    )
    (net (code "65") (name "unconnected-(R_I2-Pad6)") (class "Default")
      (node (ref "R_I2") (pin "6") (pinfunction "6_6") (pintype "passive"))
    )
    (net (code "66") (name "unconnected-(R_I2-Pad7)") (class "Default")
      (node (ref "R_I2") (pin "7") (pinfunction "7_7") (pintype "passive"))
    )
    (net (code "67") (name "unconnected-(R_I3-Pad2)") (class "Default")
      (node (ref "R_I3") (pin "2") (pinfunction "2_2") (pintype "passive"))
    )
    (net (code "68") (name "unconnected-(R_I3-Pad7)") (class "Default")
      (node (ref "R_I3") (pin "7") (pinfunction "7_7") (pintype "passive"))
    )
    (net (code "69") (name "unconnected-(U$2-PIN7_NC-PadPIN7)") (class "Default")
      (node (ref "U$2") (pin "PIN7") (pinfunction "PIN7_NC_PIN7") (pintype "bidirectional"))
    )
    (net (code "70") (name "unconnected-(U$2-PIN14_NC-PadPIN14)") (class "Default")
      (node (ref "U$2") (pin "PIN14") (pinfunction "PIN14_NC_PIN14") (pintype "bidirectional"))
    )
    (net (code "71") (name "unconnected-(U$2-PIN18_NC-PadPIN18)") (class "Default")
      (node (ref "U$2") (pin "PIN18") (pinfunction "PIN18_NC_PIN18") (pintype "bidirectional"))
    )
    (net (code "72") (name "unconnected-(U$3-6_FAULT-PadP$6)") (class "Default")
      (node (ref "U$3") (pin "P$6") (pinfunction "6_FAULT_P$6") (pintype "bidirectional"))
    )
    (net (code "73") (name "unconnected-(U$8-PadP$3)") (class "Default")
      (node (ref "U$8") (pin "P$3") (pinfunction "P$3_P$3") (pintype "bidirectional"))
    )
    (net (code "74") (name "unconnected-(U$8-PadP$4)") (class "Default")
      (node (ref "U$8") (pin "P$4") (pinfunction "P$4_P$4") (pintype "bidirectional"))
    )
  )
)
